# Pulse_generator.net
KiCad netlist of a schematic drawn in EAGLE
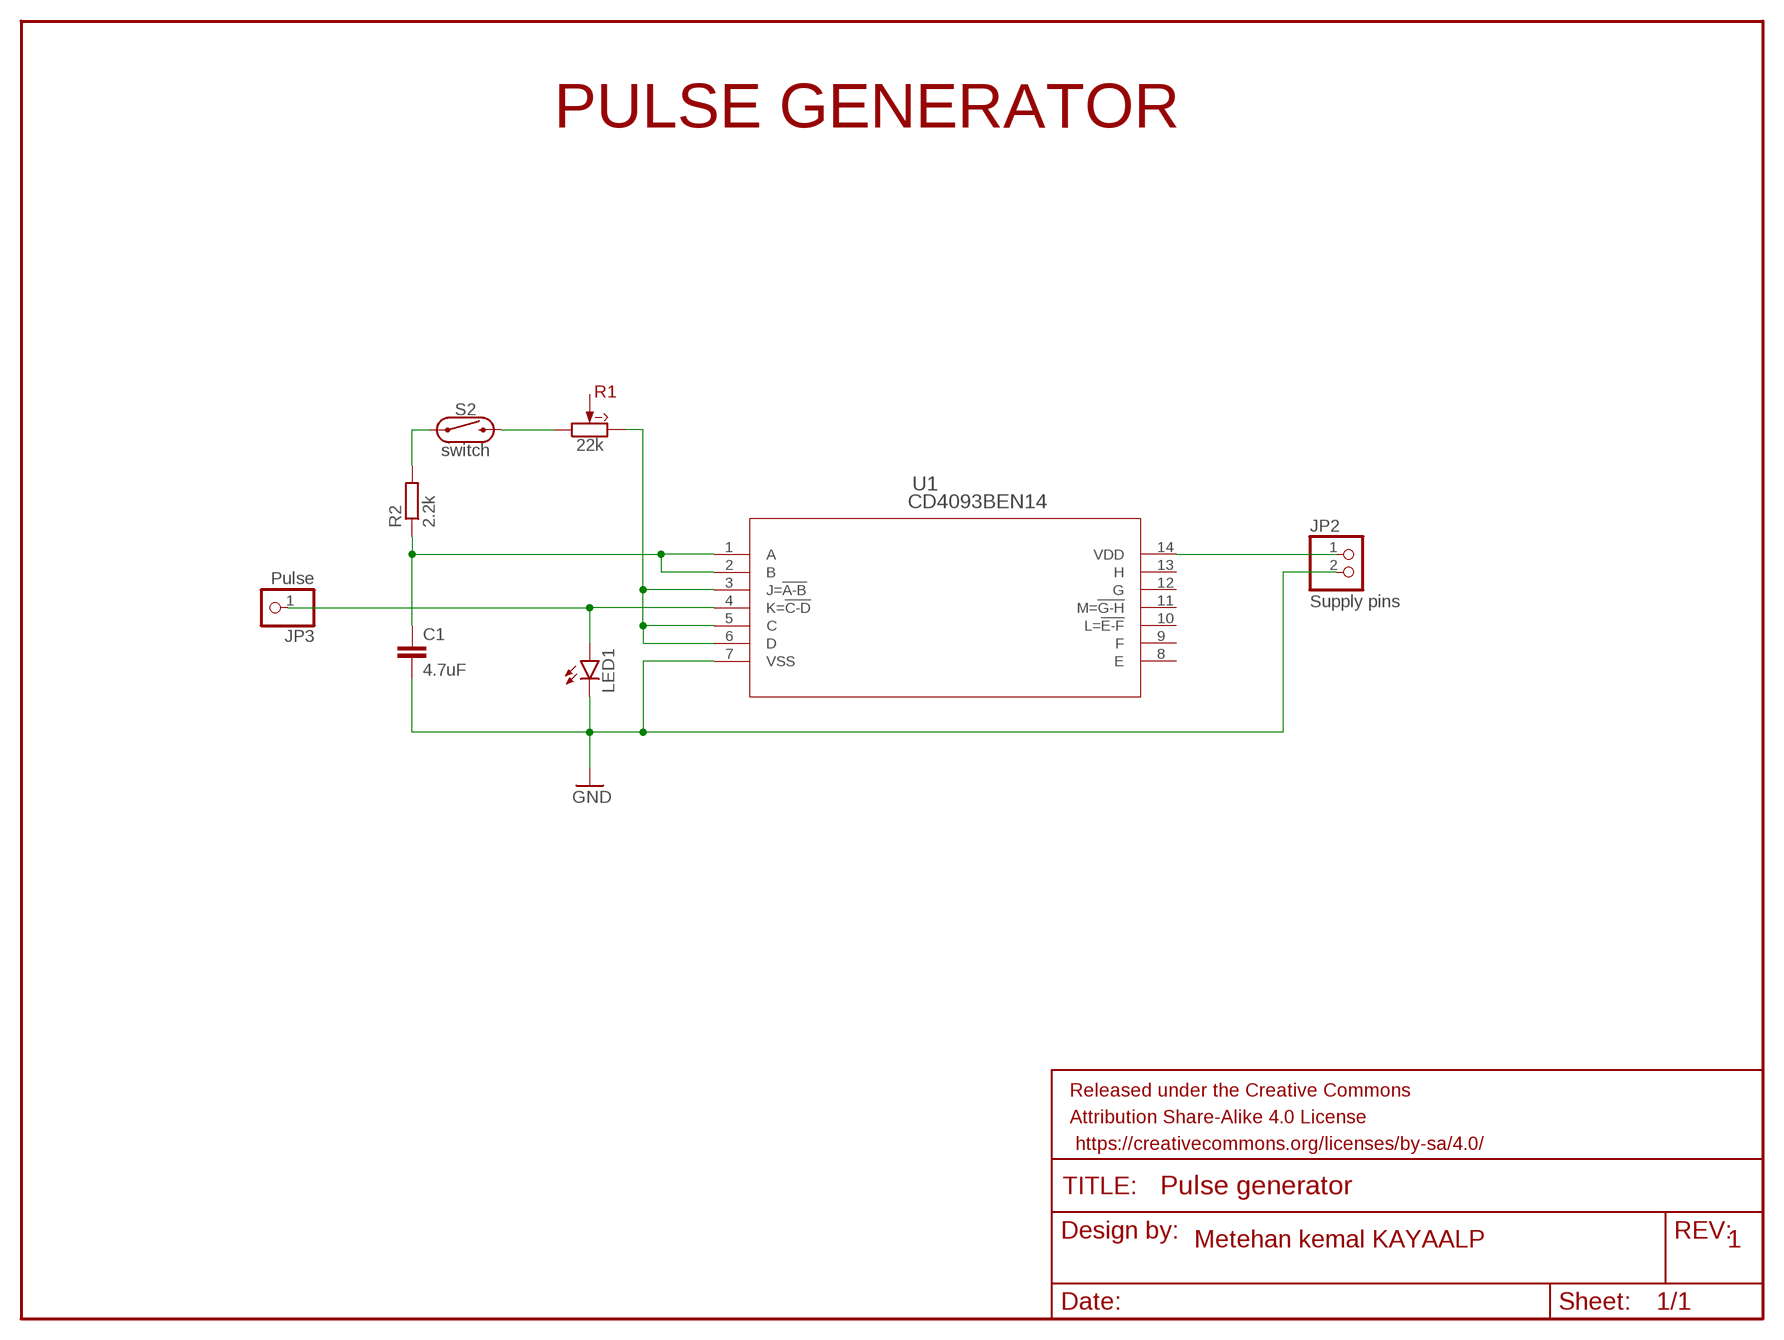
[diagram p0: schematic, sheet 1]

(export (version "E")
  (design (tool "Eeschema 10.0.6"))
  (components
    (comp (ref "C1")
      (value "4.7uF")
      (footprint "eagle-import:C2.5-3")
      (libsource (lib "eagle-import") (part "C2,5-3"))
    )
    (comp (ref "FRAME1")
      (value "FRAME-LETTER")
      (footprint "eagle-import:CREATIVE_COMMONS")
      (libsource (lib "eagle-import") (part "FRAME-LETTER"))
    )
    (comp (ref "JP2")
      (value "Supply pins")
      (footprint "eagle-import:1X02")
      (libsource (lib "eagle-import") (part "PINHD-1X2"))
    )
    (comp (ref "JP3")
      (value "Pulse")
      (footprint "eagle-import:1X01")
      (libsource (lib "eagle-import") (part "PINHD-1X1"))
    )
    (comp (ref "LED1")
      (value "LED5MM")
      (footprint "eagle-import:LED5MM")
      (libsource (lib "eagle-import") (part "LED5MM"))
    )
    (comp (ref "R1")
      (value "22k")
      (footprint "eagle-import:PTD901")
      (libsource (lib "eagle-import") (part "?(PTD90)A1M"))
    )
    (comp (ref "R2")
      (value "2.2k")
      (footprint "eagle-import:0204V")
      (libsource (lib "eagle-import") (part "R-EU_0204/2V"))
    )
    (comp (ref "S2")
      (value "switch")
      (footprint "eagle-import:REED_SWITCH_PLASTIC")
      (libsource (lib "eagle-import") (part "REED_SWITCH-PTH-INSULATED"))
    )
    (comp (ref "U1")
      (value "CD4093BEN14")
      (footprint "eagle-import:N14")
      (fields
        (field (name "MANUFACTURER_PART_NUMBER") "CD4093BE")
        (field (name "COPYRIGHT") "Copyright (C) 2023 Ultra Librarian. All rights reserved.")
      )
      (libsource (lib "eagle-import") (part "CD4093BEN14"))
    )
  )
  (nets
    (net (code "1") (name "GND") (class "Default")
      (node (ref "C1") (pin "2") (pinfunction "2_2") (pintype "passive"))
      (node (ref "JP2") (pin "2") (pinfunction "2_2") (pintype "passive"))
      (node (ref "LED1") (pin "K") (pinfunction "C_K") (pintype "passive"))
      (node (ref "U1") (pin "7") (pinfunction "VSS_7") (pintype "power_in"))
    )
    (net (code "2") (name "Net-(R1-CCW)") (class "Default")
      (node (ref "R1") (pin "1") (pinfunction "CCW_1") (pintype "passive"))
      (node (ref "S2") (pin "P$2") (pinfunction "2_P$2") (pintype "passive"))
    )
    (net (code "3") (name "Net-(R1-CW)") (class "Default")
      (node (ref "R1") (pin "3") (pinfunction "CW_3") (pintype "passive"))
      (node (ref "U1") (pin "3") (pinfunction "J=~{A-B}_3") (pintype "passive"))
      (node (ref "U1") (pin "5") (pinfunction "C_5") (pintype "passive"))
      (node (ref "U1") (pin "6") (pinfunction "D_6") (pintype "passive"))
    )
    (net (code "4") (name "Net-(S2-1)") (class "Default")
      (node (ref "R2") (pin "2") (pinfunction "2_2") (pintype "passive"))
      (node (ref "S2") (pin "P$1") (pinfunction "1_P$1") (pintype "passive"))
    )
    (net (code "5") (name "Net-(U1-A)") (class "Default")
      (node (ref "C1") (pin "1") (pinfunction "1_1") (pintype "passive"))
      (node (ref "R2") (pin "1") (pinfunction "1_1") (pintype "passive"))
      (node (ref "U1") (pin "1") (pinfunction "A_1") (pintype "passive"))
      (node (ref "U1") (pin "2") (pinfunction "B_2") (pintype "passive"))
    )
    (net (code "6") (name "Net-(U1-K=~{C-D})") (class "Default")
      (node (ref "JP3") (pin "1") (pinfunction "1_1") (pintype "passive"))
      (node (ref "LED1") (pin "A") (pinfunction "A_A") (pintype "passive"))
      (node (ref "U1") (pin "4") (pinfunction "K=~{C-D}_4") (pintype "passive"))
    )
    (net (code "7") (name "Net-(U1-VDD)") (class "Default")
      (node (ref "JP2") (pin "1") (pinfunction "1_1") (pintype "passive"))
      (node (ref "U1") (pin "14") (pinfunction "VDD_14") (pintype "power_in"))
    )
    (net (code "8") (name "unconnected-(R1-W-Pad2)") (class "Default")
      (node (ref "R1") (pin "2") (pinfunction "W_2") (pintype "passive"))
    )
    (net (code "9") (name "unconnected-(U1-E-Pad8)") (class "Default")
      (node (ref "U1") (pin "8") (pinfunction "E_8") (pintype "passive"))
    )
    (net (code "10") (name "unconnected-(U1-F-Pad9)") (class "Default")
      (node (ref "U1") (pin "9") (pinfunction "F_9") (pintype "passive"))
    )
    (net (code "11") (name "unconnected-(U1-G-Pad12)") (class "Default")
      (node (ref "U1") (pin "12") (pinfunction "G_12") (pintype "passive"))
    )
    (net (code "12") (name "unconnected-(U1-H-Pad13)") (class "Default")
      (node (ref "U1") (pin "13") (pinfunction "H_13") (pintype "passive"))
    )
    (net (code "13") (name "unconnected-(U1-L=~{E-F}-Pad10)") (class "Default")
      (node (ref "U1") (pin "10") (pinfunction "L=~{E-F}_10") (pintype "passive"))
    )
    (net (code "14") (name "unconnected-(U1-M=~{G-H}-Pad11)") (class "Default")
      (node (ref "U1") (pin "11") (pinfunction "M=~{G-H}_11") (pintype "passive"))
    )
  )
)
